# FRONT_INTF.net
KiCad netlist of a schematic drawn in Altium Designer
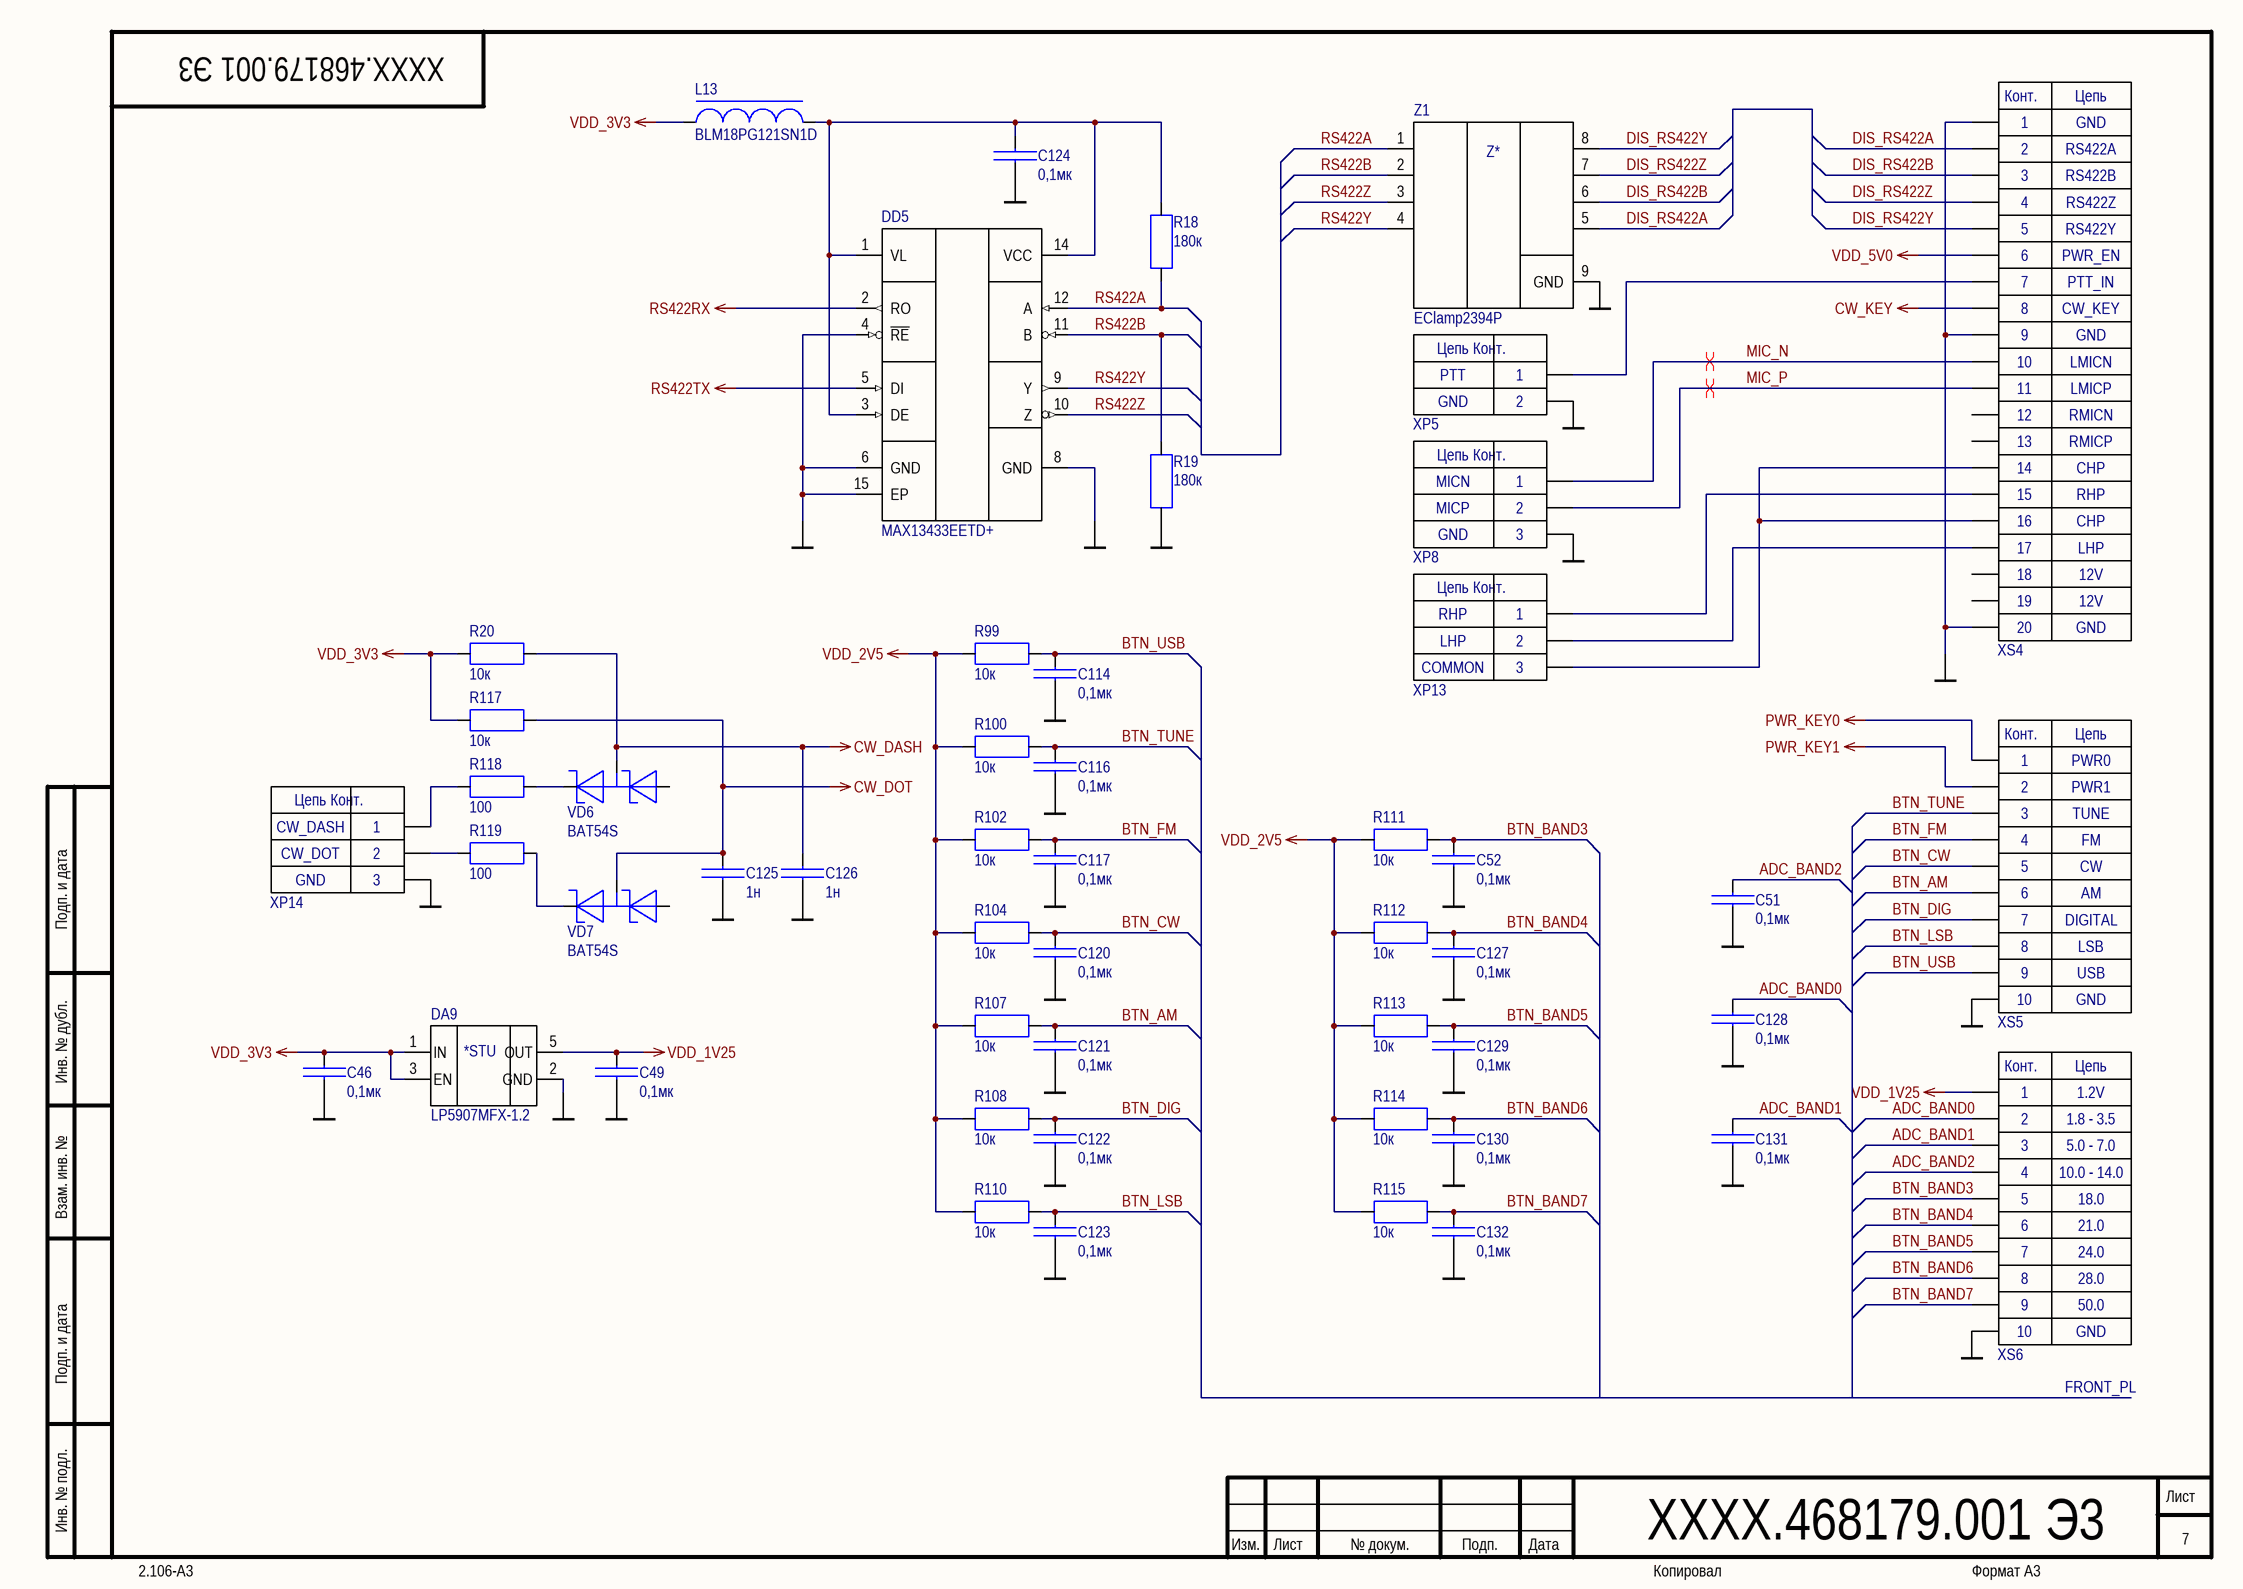
[diagram p0: FRONT_INTF.SchDoc]

(export (version "E")
  (design (tool "Eeschema 10.0.6"))
  (components
    (comp (ref "C46")
      (value "CC0402KRX5R6BB104")
      (footprint "CAPC1005X05L")
      (description "ЧИП конденсатор")
      (fields
        (field (name "NOMINAL") "0,1мк")
        (field (name "MANUFACTURER") "Yageo")
        (field (name "TOLERANCE") "10%")
      )
      (libsource (lib "Database_Gost") (part "Capacitor const"))
    )
    (comp (ref "C49")
      (value "CC0402KRX5R6BB104")
      (footprint "CAPC1005X05L")
      (description "ЧИП конденсатор")
      (fields
        (field (name "NOMINAL") "0,1мк")
        (field (name "MANUFACTURER") "Yageo")
        (field (name "TOLERANCE") "10%")
      )
      (libsource (lib "Database_Gost") (part "Capacitor const"))
    )
    (comp (ref "C51")
      (value "CC0402KRX5R6BB104")
      (footprint "CAPC1005X05L")
      (description "ЧИП конденсатор")
      (fields
        (field (name "NOMINAL") "0,1мк")
        (field (name "MANUFACTURER") "Yageo")
        (field (name "TOLERANCE") "10%")
      )
      (libsource (lib "Database_Gost") (part "Capacitor const"))
    )
    (comp (ref "C52")
      (value "CC0402KRX5R6BB104")
      (footprint "CAPC1005X05L")
      (description "ЧИП конденсатор")
      (fields
        (field (name "NOMINAL") "0,1мк")
        (field (name "MANUFACTURER") "Yageo")
        (field (name "TOLERANCE") "10%")
      )
      (libsource (lib "Database_Gost") (part "Capacitor const"))
    )
    (comp (ref "C114")
      (value "CC0402KRX5R6BB104")
      (footprint "CAPC1005X05L")
      (description "ЧИП конденсатор")
      (fields
        (field (name "NOMINAL") "0,1мк")
        (field (name "MANUFACTURER") "Yageo")
        (field (name "TOLERANCE") "10%")
      )
      (libsource (lib "Database_Gost") (part "Capacitor const"))
    )
    (comp (ref "C116")
      (value "CC0402KRX5R6BB104")
      (footprint "CAPC1005X05L")
      (description "ЧИП конденсатор")
      (fields
        (field (name "NOMINAL") "0,1мк")
        (field (name "MANUFACTURER") "Yageo")
        (field (name "TOLERANCE") "10%")
      )
      (libsource (lib "Database_Gost") (part "Capacitor const"))
    )
    (comp (ref "C117")
      (value "CC0402KRX5R6BB104")
      (footprint "CAPC1005X05L")
      (description "ЧИП конденсатор")
      (fields
        (field (name "NOMINAL") "0,1мк")
        (field (name "MANUFACTURER") "Yageo")
        (field (name "TOLERANCE") "10%")
      )
      (libsource (lib "Database_Gost") (part "Capacitor const"))
    )
    (comp (ref "C120")
      (value "CC0402KRX5R6BB104")
      (footprint "CAPC1005X05L")
      (description "ЧИП конденсатор")
      (fields
        (field (name "NOMINAL") "0,1мк")
        (field (name "MANUFACTURER") "Yageo")
        (field (name "TOLERANCE") "10%")
      )
      (libsource (lib "Database_Gost") (part "Capacitor const"))
    )
    (comp (ref "C121")
      (value "CC0402KRX5R6BB104")
      (footprint "CAPC1005X05L")
      (description "ЧИП конденсатор")
      (fields
        (field (name "NOMINAL") "0,1мк")
        (field (name "MANUFACTURER") "Yageo")
        (field (name "TOLERANCE") "10%")
      )
      (libsource (lib "Database_Gost") (part "Capacitor const"))
    )
    (comp (ref "C122")
      (value "CC0402KRX5R6BB104")
      (footprint "CAPC1005X05L")
      (description "ЧИП конденсатор")
      (fields
        (field (name "NOMINAL") "0,1мк")
        (field (name "MANUFACTURER") "Yageo")
        (field (name "TOLERANCE") "10%")
      )
      (libsource (lib "Database_Gost") (part "Capacitor const"))
    )
    (comp (ref "C123")
      (value "CC0402KRX5R6BB104")
      (footprint "CAPC1005X05L")
      (description "ЧИП конденсатор")
      (fields
        (field (name "NOMINAL") "0,1мк")
        (field (name "MANUFACTURER") "Yageo")
        (field (name "TOLERANCE") "10%")
      )
      (libsource (lib "Database_Gost") (part "Capacitor const"))
    )
    (comp (ref "C124")
      (value "CC0402KRX5R6BB104")
      (footprint "CAPC1005X05L")
      (description "ЧИП конденсатор")
      (fields
        (field (name "NOMINAL") "0,1мк")
        (field (name "MANUFACTURER") "Yageo")
        (field (name "TOLERANCE") "10%")
      )
      (libsource (lib "Database_Gost") (part "Capacitor const"))
    )
    (comp (ref "C125")
      (value "C0402C102J5GACTU")
      (footprint "CAPC1005X05L")
      (description "ЧИП конденсатор")
      (fields
        (field (name "NOMINAL") "1н")
        (field (name "MANUFACTURER") "Yageo")
        (field (name "TOLERANCE") "5%")
      )
      (libsource (lib "Database_Gost") (part "Capacitor const"))
    )
    (comp (ref "C126")
      (value "C0402C102J5GACTU")
      (footprint "CAPC1005X05L")
      (description "ЧИП конденсатор")
      (fields
        (field (name "NOMINAL") "1н")
        (field (name "MANUFACTURER") "Yageo")
        (field (name "TOLERANCE") "5%")
      )
      (libsource (lib "Database_Gost") (part "Capacitor const"))
    )
    (comp (ref "C127")
      (value "CC0402KRX5R6BB104")
      (footprint "CAPC1005X05L")
      (description "ЧИП конденсатор")
      (fields
        (field (name "NOMINAL") "0,1мк")
        (field (name "MANUFACTURER") "Yageo")
        (field (name "TOLERANCE") "10%")
      )
      (libsource (lib "Database_Gost") (part "Capacitor const"))
    )
    (comp (ref "C128")
      (value "CC0402KRX5R6BB104")
      (footprint "CAPC1005X05L")
      (description "ЧИП конденсатор")
      (fields
        (field (name "NOMINAL") "0,1мк")
        (field (name "MANUFACTURER") "Yageo")
        (field (name "TOLERANCE") "10%")
      )
      (libsource (lib "Database_Gost") (part "Capacitor const"))
    )
    (comp (ref "C129")
      (value "CC0402KRX5R6BB104")
      (footprint "CAPC1005X05L")
      (description "ЧИП конденсатор")
      (fields
        (field (name "NOMINAL") "0,1мк")
        (field (name "MANUFACTURER") "Yageo")
        (field (name "TOLERANCE") "10%")
      )
      (libsource (lib "Database_Gost") (part "Capacitor const"))
    )
    (comp (ref "C130")
      (value "CC0402KRX5R6BB104")
      (footprint "CAPC1005X05L")
      (description "ЧИП конденсатор")
      (fields
        (field (name "NOMINAL") "0,1мк")
        (field (name "MANUFACTURER") "Yageo")
        (field (name "TOLERANCE") "10%")
      )
      (libsource (lib "Database_Gost") (part "Capacitor const"))
    )
    (comp (ref "C131")
      (value "CC0402KRX5R6BB104")
      (footprint "CAPC1005X05L")
      (description "ЧИП конденсатор")
      (fields
        (field (name "NOMINAL") "0,1мк")
        (field (name "MANUFACTURER") "Yageo")
        (field (name "TOLERANCE") "10%")
      )
      (libsource (lib "Database_Gost") (part "Capacitor const"))
    )
    (comp (ref "C132")
      (value "CC0402KRX5R6BB104")
      (footprint "CAPC1005X05L")
      (description "ЧИП конденсатор")
      (fields
        (field (name "NOMINAL") "0,1мк")
        (field (name "MANUFACTURER") "Yageo")
        (field (name "TOLERANCE") "10%")
      )
      (libsource (lib "Database_Gost") (part "Capacitor const"))
    )
    (comp (ref "DA9")
      (value "LP5907MFX-1.2")
      (footprint "SOT95P280X145-5L")
      (description "LP5907 250mA, Low-Noise, Low-IQ LDO")
      (fields (field (name "MANUFACTURER") "TI"))
      (libsource (lib "Database_Gost") (part "LP5907MFX"))
    )
    (comp (ref "DD5")
      (value "MAX13433EETD+")
      (footprint "SON40P300X80_HS-15L")
      (description "RS-422 Transceivers with Low-Voltage Logic Interface 16M")
      (fields (field (name "MANUFACTURER") "AD"))
      (libsource (lib "Chips_single") (part "MAX13433EETD+"))
    )
    (comp (ref "L13")
      (value "BLM18PG121SN1D")
      (footprint "INDC1608X05L")
      (description "Chip Ferrite Beads (0603 Size)")
      (fields (field (name "NOMINAL") "BLM18PG121SN1D") (field (name "MANUFACTURER") "Murata"))
      (libsource (lib "Database_Gost") (part "Inductor ferr"))
    )
    (comp (ref "R18")
      (value "RC0402JR-07180KL")
      (footprint "RESC1005X04L")
      (description "ЧИП резистор")
      (fields
        (field (name "NOMINAL") "180к")
        (field (name "MANUFACTURER") "Yageo")
        (field (name "TOLERANCE") "5%")
      )
      (libsource (lib "Database_Gost") (part "Resistor const"))
    )
    (comp (ref "R19")
      (value "RC0402JR-07180KL")
      (footprint "RESC1005X04L")
      (description "ЧИП резистор")
      (fields
        (field (name "NOMINAL") "180к")
        (field (name "MANUFACTURER") "Yageo")
        (field (name "TOLERANCE") "5%")
      )
      (libsource (lib "Database_Gost") (part "Resistor const"))
    )
    (comp (ref "R20")
      (value "RC0402JR-0710KL")
      (footprint "RESC1005X04L")
      (description "ЧИП резистор")
      (fields
        (field (name "NOMINAL") "10к")
        (field (name "MANUFACTURER") "Yageo")
        (field (name "TOLERANCE") "5%")
      )
      (libsource (lib "Database_Gost") (part "Resistor const"))
    )
    (comp (ref "R99")
      (value "RC0402JR-0710KL")
      (footprint "RESC1005X04L")
      (description "ЧИП резистор")
      (fields
        (field (name "NOMINAL") "10к")
        (field (name "MANUFACTURER") "Yageo")
        (field (name "TOLERANCE") "5%")
      )
      (libsource (lib "Database_Gost") (part "Resistor const"))
    )
    (comp (ref "R100")
      (value "RC0402JR-0710KL")
      (footprint "RESC1005X04L")
      (description "ЧИП резистор")
      (fields
        (field (name "NOMINAL") "10к")
        (field (name "MANUFACTURER") "Yageo")
        (field (name "TOLERANCE") "5%")
      )
      (libsource (lib "Database_Gost") (part "Resistor const"))
    )
    (comp (ref "R102")
      (value "RC0402JR-0710KL")
      (footprint "RESC1005X04L")
      (description "ЧИП резистор")
      (fields
        (field (name "NOMINAL") "10к")
        (field (name "MANUFACTURER") "Yageo")
        (field (name "TOLERANCE") "5%")
      )
      (libsource (lib "Database_Gost") (part "Resistor const"))
    )
    (comp (ref "R104")
      (value "RC0402JR-0710KL")
      (footprint "RESC1005X04L")
      (description "ЧИП резистор")
      (fields
        (field (name "NOMINAL") "10к")
        (field (name "MANUFACTURER") "Yageo")
        (field (name "TOLERANCE") "5%")
      )
      (libsource (lib "Database_Gost") (part "Resistor const"))
    )
    (comp (ref "R107")
      (value "RC0402JR-0710KL")
      (footprint "RESC1005X04L")
      (description "ЧИП резистор")
      (fields
        (field (name "NOMINAL") "10к")
        (field (name "MANUFACTURER") "Yageo")
        (field (name "TOLERANCE") "5%")
      )
      (libsource (lib "Database_Gost") (part "Resistor const"))
    )
    (comp (ref "R108")
      (value "RC0402JR-0710KL")
      (footprint "RESC1005X04L")
      (description "ЧИП резистор")
      (fields
        (field (name "NOMINAL") "10к")
        (field (name "MANUFACTURER") "Yageo")
        (field (name "TOLERANCE") "5%")
      )
      (libsource (lib "Database_Gost") (part "Resistor const"))
    )
    (comp (ref "R110")
      (value "RC0402JR-0710KL")
      (footprint "RESC1005X04L")
      (description "ЧИП резистор")
      (fields
        (field (name "NOMINAL") "10к")
        (field (name "MANUFACTURER") "Yageo")
        (field (name "TOLERANCE") "5%")
      )
      (libsource (lib "Database_Gost") (part "Resistor const"))
    )
    (comp (ref "R111")
      (value "RC0402JR-0710KL")
      (footprint "RESC1005X04L")
      (description "ЧИП резистор")
      (fields
        (field (name "NOMINAL") "10к")
        (field (name "MANUFACTURER") "Yageo")
        (field (name "TOLERANCE") "5%")
      )
      (libsource (lib "Database_Gost") (part "Resistor const"))
    )
    (comp (ref "R112")
      (value "RC0402JR-0710KL")
      (footprint "RESC1005X04L")
      (description "ЧИП резистор")
      (fields
        (field (name "NOMINAL") "10к")
        (field (name "MANUFACTURER") "Yageo")
        (field (name "TOLERANCE") "5%")
      )
      (libsource (lib "Database_Gost") (part "Resistor const"))
    )
    (comp (ref "R113")
      (value "RC0402JR-0710KL")
      (footprint "RESC1005X04L")
      (description "ЧИП резистор")
      (fields
        (field (name "NOMINAL") "10к")
        (field (name "MANUFACTURER") "Yageo")
        (field (name "TOLERANCE") "5%")
      )
      (libsource (lib "Database_Gost") (part "Resistor const"))
    )
    (comp (ref "R114")
      (value "RC0402JR-0710KL")
      (footprint "RESC1005X04L")
      (description "ЧИП резистор")
      (fields
        (field (name "NOMINAL") "10к")
        (field (name "MANUFACTURER") "Yageo")
        (field (name "TOLERANCE") "5%")
      )
      (libsource (lib "Database_Gost") (part "Resistor const"))
    )
    (comp (ref "R115")
      (value "RC0402JR-0710KL")
      (footprint "RESC1005X04L")
      (description "ЧИП резистор")
      (fields
        (field (name "NOMINAL") "10к")
        (field (name "MANUFACTURER") "Yageo")
        (field (name "TOLERANCE") "5%")
      )
      (libsource (lib "Database_Gost") (part "Resistor const"))
    )
    (comp (ref "R117")
      (value "RC0402JR-0710KL")
      (footprint "RESC1005X04L")
      (description "ЧИП резистор")
      (fields
        (field (name "NOMINAL") "10к")
        (field (name "MANUFACTURER") "Yageo")
        (field (name "TOLERANCE") "5%")
      )
      (libsource (lib "Database_Gost") (part "Resistor const"))
    )
    (comp (ref "R118")
      (value "RC0402JR-07100RL")
      (footprint "RESC1005X04L")
      (description "ЧИП резистор")
      (fields
        (field (name "NOMINAL") "100")
        (field (name "MANUFACTURER") "Yageo")
        (field (name "TOLERANCE") "5%")
      )
      (libsource (lib "Database_Gost") (part "Resistor const"))
    )
    (comp (ref "R119")
      (value "RC0402JR-07100RL")
      (footprint "RESC1005X04L")
      (description "ЧИП резистор")
      (fields
        (field (name "NOMINAL") "100")
        (field (name "MANUFACTURER") "Yageo")
        (field (name "TOLERANCE") "5%")
      )
      (libsource (lib "Database_Gost") (part "Resistor const"))
    )
    (comp (ref "VD6")
      (value "BAT54S")
      (footprint "SOT95P240X120-3L")
      (description "SCHOTTKY DIODE")
      (fields (field (name "MANUFACTURER") "International Rectifier"))
      (libsource (lib "Database_Gost") (part "DiodeShottkyAKAK"))
    )
    (comp (ref "VD7")
      (value "BAT54S")
      (footprint "SOT95P240X120-3L")
      (description "SCHOTTKY DIODE")
      (fields (field (name "MANUFACTURER") "International Rectifier"))
      (libsource (lib "Database_Gost") (part "DiodeShottkyAKAK"))
    )
    (comp (ref "XP5")
      (value "WB-02")
      (footprint "WB-02 (MW-2M) PITCH 2.00MM")
      (description "WB-02 (MW-2M) pitch 2.00mm\r\nDS1066-02M")
      (libsource (lib "Connectors") (part "WB-02"))
    )
    (comp (ref "XP8")
      (value "WB-03")
      (footprint "WB-03 (MW-3M) PITCH 2.00MM")
      (description "WB-03(MW-3M) pitch 2.00mm\r\nDS1066-03M")
      (libsource (lib "Connectors") (part "WB-03"))
    )
    (comp (ref "XP13")
      (value "WB-03")
      (footprint "WB-03 (MW-3M) PITCH 2.00MM")
      (description "WB-03(MW-3M) pitch 2.00mm\r\nDS1066-03M")
      (libsource (lib "Connectors") (part "WB-03"))
    )
    (comp (ref "XP14")
      (value "WB-03")
      (footprint "WB-03 (MW-3M) PITCH 2.00MM")
      (description "WB-03(MW-3M) pitch 2.00mm\r\nDS1066-03M")
      (libsource (lib "Connectors") (part "WB-03"))
    )
    (comp (ref "XS4")
      (value "FH12-20S-0.5SVA")
      (footprint "FH12-20S-0.5SVA")
      (description "FPC Connectors, Flex-to-Board, 20 Position, .5mm [.02in]")
      (fields (field (name "MANUFACTURER") "Hirose"))
      (libsource (lib "Connectors") (part "FH12-20S-0.5SVA"))
    )
    (comp (ref "XS5")
      (value "FH12-10S-0.5SVA")
      (footprint "FH12-10S-0.5SH")
      (fields (field (name "MANUFACTURER") "Hirose"))
      (libsource (lib "Connectors") (part "FH12-10S-0.5SVA"))
    )
    (comp (ref "XS6")
      (value "FH12-10S-0.5SVA")
      (footprint "FH12-10S-0.5SH")
      (fields (field (name "MANUFACTURER") "Hirose"))
      (libsource (lib "Connectors") (part "FH12-10S-0.5SVA"))
    )
    (comp (ref "Z1")
      (value "EClamp2394P")
      (footprint "SON50P160X65_HS-9N")
      (description "ESD-EMI 4-line Protection for Color LCD Interfaces")
      (fields (field (name "MANUFACTURER") "SEMTECH") (field (name "MANUFACTURERPARTNUMBER") "ECLAMP2394P"))
      (libsource (lib "Chips_single") (part "EClamp2394P"))
    )
  )
  (nets
    (net (code "1") (name "/ADC_BAND0") (class "Default")
      (node (ref "C128") (pin "1") (pinfunction "1_1") (pintype "passive"))
      (node (ref "XS6") (pin "2") (pinfunction "2_2") (pintype "passive"))
    )
    (net (code "2") (name "/ADC_BAND1") (class "Default")
      (node (ref "C131") (pin "1") (pinfunction "1_1") (pintype "passive"))
      (node (ref "XS6") (pin "3") (pinfunction "3_3") (pintype "passive"))
    )
    (net (code "3") (name "/ADC_BAND2") (class "Default")
      (node (ref "C51") (pin "1") (pinfunction "1_1") (pintype "passive"))
      (node (ref "XS6") (pin "4") (pinfunction "4_4") (pintype "passive"))
    )
    (net (code "4") (name "/BTN_AM") (class "Default")
      (node (ref "C121") (pin "1") (pinfunction "1_1") (pintype "passive"))
      (node (ref "R107") (pin "1") (pinfunction "1_1") (pintype "passive"))
      (node (ref "XS5") (pin "6") (pinfunction "6_6") (pintype "passive"))
    )
    (net (code "5") (name "/BTN_BAND3") (class "Default")
      (node (ref "C52") (pin "1") (pinfunction "1_1") (pintype "passive"))
      (node (ref "R111") (pin "1") (pinfunction "1_1") (pintype "passive"))
      (node (ref "XS6") (pin "5") (pinfunction "5_5") (pintype "passive"))
    )
    (net (code "6") (name "/BTN_BAND4") (class "Default")
      (node (ref "C127") (pin "1") (pinfunction "1_1") (pintype "passive"))
      (node (ref "R112") (pin "1") (pinfunction "1_1") (pintype "passive"))
      (node (ref "XS6") (pin "6") (pinfunction "6_6") (pintype "passive"))
    )
    (net (code "7") (name "/BTN_BAND5") (class "Default")
      (node (ref "C129") (pin "1") (pinfunction "1_1") (pintype "passive"))
      (node (ref "R113") (pin "1") (pinfunction "1_1") (pintype "passive"))
      (node (ref "XS6") (pin "7") (pinfunction "7_7") (pintype "passive"))
    )
    (net (code "8") (name "/BTN_BAND6") (class "Default")
      (node (ref "C130") (pin "1") (pinfunction "1_1") (pintype "passive"))
      (node (ref "R114") (pin "1") (pinfunction "1_1") (pintype "passive"))
      (node (ref "XS6") (pin "8") (pinfunction "8_8") (pintype "passive"))
    )
    (net (code "9") (name "/BTN_BAND7") (class "Default")
      (node (ref "C132") (pin "1") (pinfunction "1_1") (pintype "passive"))
      (node (ref "R115") (pin "1") (pinfunction "1_1") (pintype "passive"))
      (node (ref "XS6") (pin "9") (pinfunction "9_9") (pintype "passive"))
    )
    (net (code "10") (name "/BTN_CW") (class "Default")
      (node (ref "C120") (pin "1") (pinfunction "1_1") (pintype "passive"))
      (node (ref "R104") (pin "1") (pinfunction "1_1") (pintype "passive"))
      (node (ref "XS5") (pin "5") (pinfunction "5_5") (pintype "passive"))
    )
    (net (code "11") (name "/BTN_DIG") (class "Default")
      (node (ref "C122") (pin "1") (pinfunction "1_1") (pintype "passive"))
      (node (ref "R108") (pin "1") (pinfunction "1_1") (pintype "passive"))
      (node (ref "XS5") (pin "7") (pinfunction "7_7") (pintype "passive"))
    )
    (net (code "12") (name "/BTN_FM") (class "Default")
      (node (ref "C117") (pin "1") (pinfunction "1_1") (pintype "passive"))
      (node (ref "R102") (pin "1") (pinfunction "1_1") (pintype "passive"))
      (node (ref "XS5") (pin "4") (pinfunction "4_4") (pintype "passive"))
    )
    (net (code "13") (name "/BTN_LSB") (class "Default")
      (node (ref "C123") (pin "1") (pinfunction "1_1") (pintype "passive"))
      (node (ref "R110") (pin "1") (pinfunction "1_1") (pintype "passive"))
      (node (ref "XS5") (pin "8") (pinfunction "8_8") (pintype "passive"))
    )
    (net (code "14") (name "/BTN_TUNE") (class "Default")
      (node (ref "C116") (pin "1") (pinfunction "1_1") (pintype "passive"))
      (node (ref "R100") (pin "1") (pinfunction "1_1") (pintype "passive"))
      (node (ref "XS5") (pin "3") (pinfunction "3_3") (pintype "passive"))
    )
    (net (code "15") (name "/BTN_USB") (class "Default")
      (node (ref "C114") (pin "1") (pinfunction "1_1") (pintype "passive"))
      (node (ref "R99") (pin "1") (pinfunction "1_1") (pintype "passive"))
      (node (ref "XS5") (pin "9") (pinfunction "9_9") (pintype "passive"))
    )
    (net (code "16") (name "/DIS_RS422A") (class "Default")
      (node (ref "XS4") (pin "2") (pinfunction "2_2") (pintype "passive"))
      (node (ref "Z1") (pin "5") (pintype "passive"))
    )
    (net (code "17") (name "/DIS_RS422B") (class "Default")
      (node (ref "XS4") (pin "3") (pinfunction "3_3") (pintype "passive"))
      (node (ref "Z1") (pin "6") (pintype "passive"))
    )
    (net (code "18") (name "/DIS_RS422Y") (class "Default")
      (node (ref "XS4") (pin "5") (pinfunction "5_5") (pintype "passive"))
      (node (ref "Z1") (pin "8") (pintype "passive"))
    )
    (net (code "19") (name "/DIS_RS422Z") (class "Default")
      (node (ref "XS4") (pin "4") (pinfunction "4_4") (pintype "passive"))
      (node (ref "Z1") (pin "7") (pintype "passive"))
    )
    (net (code "20") (name "/MIC_N") (class "Default")
      (node (ref "XP8") (pin "1") (pinfunction "1_1") (pintype "passive"))
      (node (ref "XS4") (pin "10") (pinfunction "10_10") (pintype "passive"))
    )
    (net (code "21") (name "/MIC_P") (class "Default")
      (node (ref "XP8") (pin "2") (pinfunction "2_2") (pintype "passive"))
      (node (ref "XS4") (pin "11") (pinfunction "11_11") (pintype "passive"))
    )
    (net (code "22") (name "/RS422A") (class "Default")
      (node (ref "DD5") (pin "12") (pinfunction "A_12") (pintype "input"))
      (node (ref "R18") (pin "1") (pinfunction "1_1") (pintype "passive"))
      (node (ref "Z1") (pin "1") (pintype "passive"))
    )
    (net (code "23") (name "/RS422B") (class "Default")
      (node (ref "DD5") (pin "11") (pinfunction "B_11") (pintype "input"))
      (node (ref "R19") (pin "2") (pinfunction "2_2") (pintype "passive"))
      (node (ref "Z1") (pin "2") (pintype "passive"))
    )
    (net (code "24") (name "/RS422Y") (class "Default")
      (node (ref "DD5") (pin "9") (pinfunction "Y_9") (pintype "output"))
      (node (ref "Z1") (pin "4") (pintype "passive"))
    )
    (net (code "25") (name "/RS422Z") (class "Default")
      (node (ref "DD5") (pin "10") (pinfunction "Z_10") (pintype "output"))
      (node (ref "Z1") (pin "3") (pintype "passive"))
    )
    (net (code "26") (name "CW_DASH") (class "Default")
      (node (ref "C126") (pin "1") (pinfunction "1_1") (pintype "passive"))
      (node (ref "R20") (pin "1") (pinfunction "1_1") (pintype "passive"))
      (node (ref "VD6") (pin "1") (pintype "passive"))
    )
    (net (code "27") (name "CW_DOT") (class "Default")
      (node (ref "C125") (pin "1") (pinfunction "1_1") (pintype "passive"))
      (node (ref "R117") (pin "1") (pinfunction "1_1") (pintype "passive"))
      (node (ref "VD7") (pin "1") (pintype "passive"))
    )
    (net (code "28") (name "CW_KEY") (class "Default")
      (node (ref "XS4") (pin "8") (pinfunction "8_8") (pintype "passive"))
    )
    (net (code "29") (name "GND") (class "Default")
      (node (ref "C114") (pin "2") (pinfunction "2_2") (pintype "passive"))
      (node (ref "C116") (pin "2") (pinfunction "2_2") (pintype "passive"))
      (node (ref "C117") (pin "2") (pinfunction "2_2") (pintype "passive"))
      (node (ref "C120") (pin "2") (pinfunction "2_2") (pintype "passive"))
      (node (ref "C121") (pin "2") (pinfunction "2_2") (pintype "passive"))
      (node (ref "C122") (pin "2") (pinfunction "2_2") (pintype "passive"))
      (node (ref "C123") (pin "2") (pinfunction "2_2") (pintype "passive"))
      (node (ref "C124") (pin "1") (pinfunction "1_1") (pintype "passive"))
      (node (ref "C125") (pin "2") (pinfunction "2_2") (pintype "passive"))
      (node (ref "C126") (pin "2") (pinfunction "2_2") (pintype "passive"))
      (node (ref "C127") (pin "2") (pinfunction "2_2") (pintype "passive"))
      (node (ref "C128") (pin "2") (pinfunction "2_2") (pintype "passive"))
      (node (ref "C129") (pin "2") (pinfunction "2_2") (pintype "passive"))
      (node (ref "C130") (pin "2") (pinfunction "2_2") (pintype "passive"))
      (node (ref "C131") (pin "2") (pinfunction "2_2") (pintype "passive"))
      (node (ref "C132") (pin "2") (pinfunction "2_2") (pintype "passive"))
      (node (ref "C46") (pin "1") (pinfunction "1_1") (pintype "passive"))
      (node (ref "C49") (pin "1") (pinfunction "1_1") (pintype "passive"))
      (node (ref "C51") (pin "2") (pinfunction "2_2") (pintype "passive"))
      (node (ref "C52") (pin "2") (pinfunction "2_2") (pintype "passive"))
      (node (ref "DA9") (pin "2") (pinfunction "GND_2") (pintype "passive"))
      (node (ref "DD5") (pin "15") (pinfunction "EP_15") (pintype "passive"))
      (node (ref "DD5") (pin "4") (pinfunction "~{RE}_4") (pintype "input"))
      (node (ref "DD5") (pin "6") (pinfunction "GND_6") (pintype "passive"))
      (node (ref "DD5") (pin "8") (pinfunction "GND_8") (pintype "passive"))
      (node (ref "R19") (pin "1") (pinfunction "1_1") (pintype "passive"))
      (node (ref "XP14") (pin "3") (pinfunction "3_3") (pintype "passive"))
      (node (ref "XP5") (pin "2") (pinfunction "2_2") (pintype "passive"))
      (node (ref "XP8") (pin "3") (pinfunction "3_3") (pintype "passive"))
      (node (ref "XS4") (pin "1") (pinfunction "1_1") (pintype "passive"))
      (node (ref "XS4") (pin "20") (pinfunction "20_20") (pintype "passive"))
      (node (ref "XS4") (pin "9") (pinfunction "9_9") (pintype "passive"))
      (node (ref "XS5") (pin "10") (pinfunction "10_10") (pintype "passive"))
      (node (ref "XS6") (pin "10") (pinfunction "10_10") (pintype "passive"))
      (node (ref "Z1") (pin "9") (pinfunction "GND_9") (pintype "passive"))
    )
    (net (code "30") (name "Net-(DD5-DE)") (class "Default")
      (node (ref "C124") (pin "2") (pinfunction "2_2") (pintype "passive"))
      (node (ref "DD5") (pin "1") (pinfunction "VL_1") (pintype "passive"))
      (node (ref "DD5") (pin "14") (pinfunction "VCC_14") (pintype "passive"))
      (node (ref "DD5") (pin "3") (pinfunction "DE_3") (pintype "input"))
      (node (ref "L13") (pin "1") (pinfunction "1_1") (pintype "passive"))
      (node (ref "R18") (pin "2") (pinfunction "2_2") (pintype "passive"))
    )
    (net (code "31") (name "Net-(R118-Pad2)") (class "Default")
      (node (ref "R118") (pin "2") (pinfunction "2_2") (pintype "passive"))
      (node (ref "XP14") (pin "1") (pinfunction "1_1") (pintype "passive"))
    )
    (net (code "32") (name "Net-(R119-Pad2)") (class "Default")
      (node (ref "R119") (pin "2") (pinfunction "2_2") (pintype "passive"))
      (node (ref "XP14") (pin "2") (pinfunction "2_2") (pintype "passive"))
    )
    (net (code "33") (name "Net-(VD6-K)") (class "Default")
      (node (ref "R118") (pin "1") (pinfunction "1_1") (pintype "passive"))
      (node (ref "VD6") (pin "3") (pinfunction "K_3") (pintype "passive"))
    )
    (net (code "34") (name "Net-(VD7-K)") (class "Default")
      (node (ref "R119") (pin "1") (pinfunction "1_1") (pintype "passive"))
      (node (ref "VD7") (pin "3") (pinfunction "K_3") (pintype "passive"))
    )
    (net (code "35") (name "Net-(XP5-Pad1)") (class "Default")
      (node (ref "XP5") (pin "1") (pinfunction "1_1") (pintype "passive"))
      (node (ref "XS4") (pin "7") (pinfunction "7_7") (pintype "passive"))
    )
    (net (code "36") (name "Net-(XP13-Pad1)") (class "Default")
      (node (ref "XP13") (pin "1") (pinfunction "1_1") (pintype "passive"))
      (node (ref "XS4") (pin "15") (pinfunction "15_15") (pintype "passive"))
    )
    (net (code "37") (name "Net-(XP13-Pad2)") (class "Default")
      (node (ref "XP13") (pin "2") (pinfunction "2_2") (pintype "passive"))
      (node (ref "XS4") (pin "17") (pinfunction "17_17") (pintype "passive"))
    )
    (net (code "38") (name "Net-(XP13-Pad3)") (class "Default")
      (node (ref "XP13") (pin "3") (pinfunction "3_3") (pintype "passive"))
      (node (ref "XS4") (pin "14") (pinfunction "14_14") (pintype "passive"))
      (node (ref "XS4") (pin "16") (pinfunction "16_16") (pintype "passive"))
    )
    (net (code "39") (name "PWR_KEY0") (class "Default")
      (node (ref "XS5") (pin "1") (pinfunction "1_1") (pintype "passive"))
    )
    (net (code "40") (name "PWR_KEY1") (class "Default")
      (node (ref "XS5") (pin "2") (pinfunction "2_2") (pintype "passive"))
    )
    (net (code "41") (name "RS422RX") (class "Default")
      (node (ref "DD5") (pin "2") (pinfunction "RO_2") (pintype "output"))
    )
    (net (code "42") (name "RS422TX") (class "Default")
      (node (ref "DD5") (pin "5") (pinfunction "DI_5") (pintype "input"))
    )
    (net (code "43") (name "VDD_1V25") (class "Default")
      (node (ref "C49") (pin "2") (pinfunction "2_2") (pintype "passive"))
      (node (ref "DA9") (pin "5") (pinfunction "OUT_5") (pintype "passive"))
      (node (ref "XS6") (pin "1") (pinfunction "1_1") (pintype "passive"))
    )
    (net (code "44") (name "VDD_2V5") (class "Default")
      (node (ref "R100") (pin "2") (pinfunction "2_2") (pintype "passive"))
      (node (ref "R102") (pin "2") (pinfunction "2_2") (pintype "passive"))
      (node (ref "R104") (pin "2") (pinfunction "2_2") (pintype "passive"))
      (node (ref "R107") (pin "2") (pinfunction "2_2") (pintype "passive"))
      (node (ref "R108") (pin "2") (pinfunction "2_2") (pintype "passive"))
      (node (ref "R110") (pin "2") (pinfunction "2_2") (pintype "passive"))
      (node (ref "R111") (pin "2") (pinfunction "2_2") (pintype "passive"))
      (node (ref "R112") (pin "2") (pinfunction "2_2") (pintype "passive"))
      (node (ref "R113") (pin "2") (pinfunction "2_2") (pintype "passive"))
      (node (ref "R114") (pin "2") (pinfunction "2_2") (pintype "passive"))
      (node (ref "R115") (pin "2") (pinfunction "2_2") (pintype "passive"))
      (node (ref "R99") (pin "2") (pinfunction "2_2") (pintype "passive"))
    )
    (net (code "45") (name "VDD_3V3") (class "Default")
      (node (ref "C46") (pin "2") (pinfunction "2_2") (pintype "passive"))
      (node (ref "DA9") (pin "1") (pinfunction "IN_1") (pintype "passive"))
      (node (ref "DA9") (pin "3") (pinfunction "EN_3") (pintype "passive"))
      (node (ref "L13") (pin "2") (pinfunction "2_2") (pintype "passive"))
      (node (ref "R117") (pin "2") (pinfunction "2_2") (pintype "passive"))
      (node (ref "R20") (pin "2") (pinfunction "2_2") (pintype "passive"))
    )
    (net (code "46") (name "VDD_5V0") (class "Default")
      (node (ref "XS4") (pin "6") (pinfunction "6_6") (pintype "passive"))
    )
    (net (code "47") (name "unconnected-(VD6-A-Pad2)") (class "Default")
      (node (ref "VD6") (pin "2") (pinfunction "A_2") (pintype "passive"))
    )
    (net (code "48") (name "unconnected-(VD7-A-Pad2)") (class "Default")
      (node (ref "VD7") (pin "2") (pinfunction "A_2") (pintype "passive"))
    )
    (net (code "49") (name "unconnected-(XS4-Pad12)") (class "Default")
      (node (ref "XS4") (pin "12") (pinfunction "12_12") (pintype "passive"))
    )
    (net (code "50") (name "unconnected-(XS4-Pad13)") (class "Default")
      (node (ref "XS4") (pin "13") (pinfunction "13_13") (pintype "passive"))
    )
    (net (code "51") (name "unconnected-(XS4-Pad18)") (class "Default")
      (node (ref "XS4") (pin "18") (pinfunction "18_18") (pintype "passive"))
    )
    (net (code "52") (name "unconnected-(XS4-Pad19)") (class "Default")
      (node (ref "XS4") (pin "19") (pinfunction "19_19") (pintype "passive"))
    )
  )
)
